# freesoc_1_1.net
KiCad netlist of a schematic drawn in EAGLE
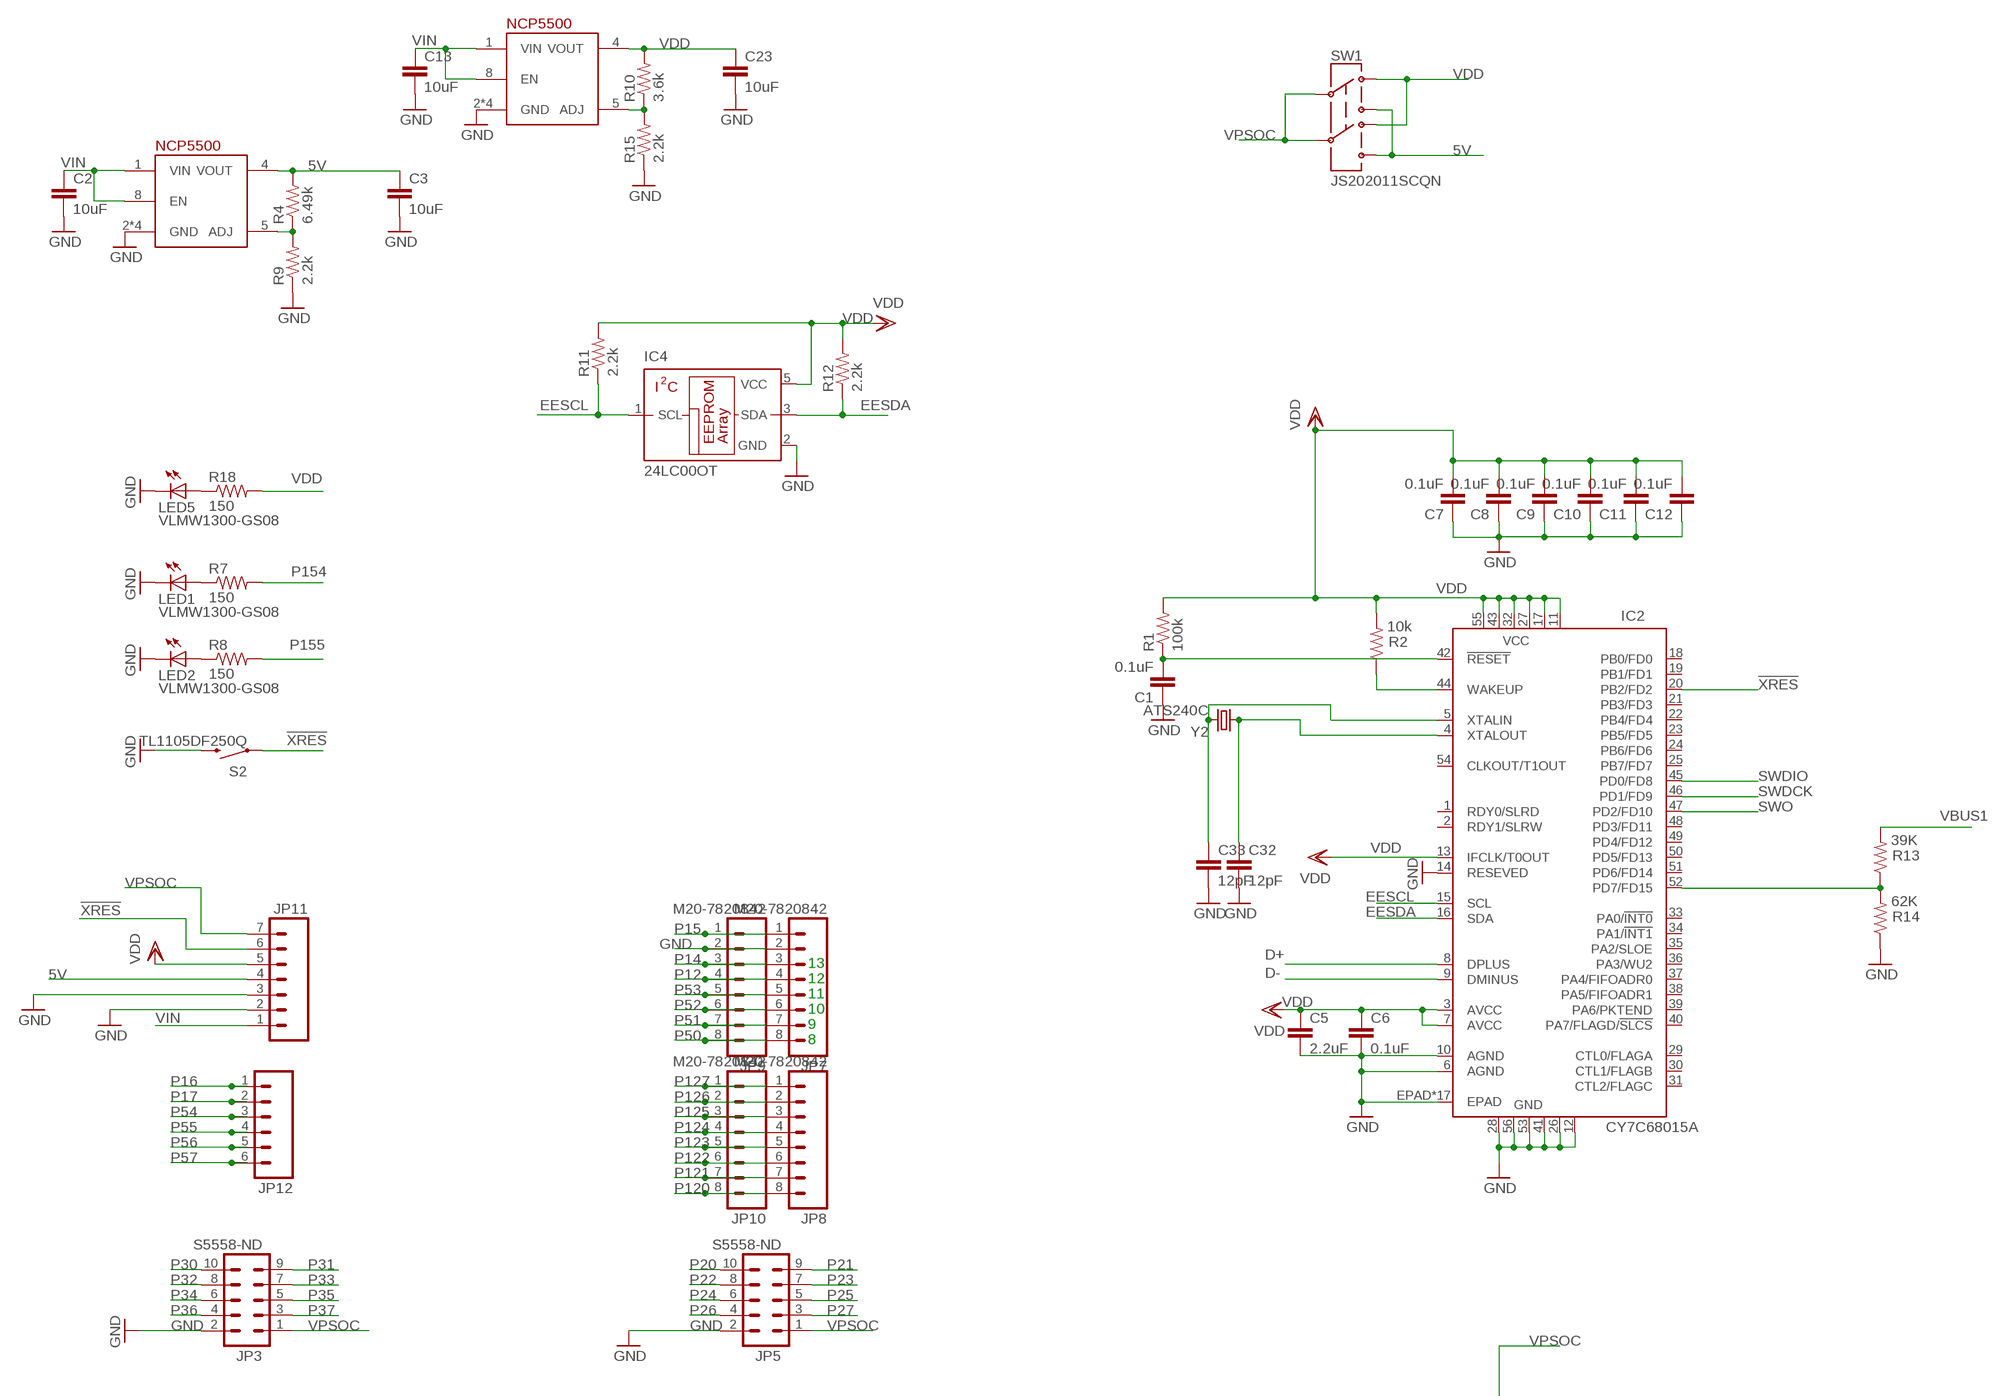
[diagram p0: schematic, sheet 1, part 1 of 2]
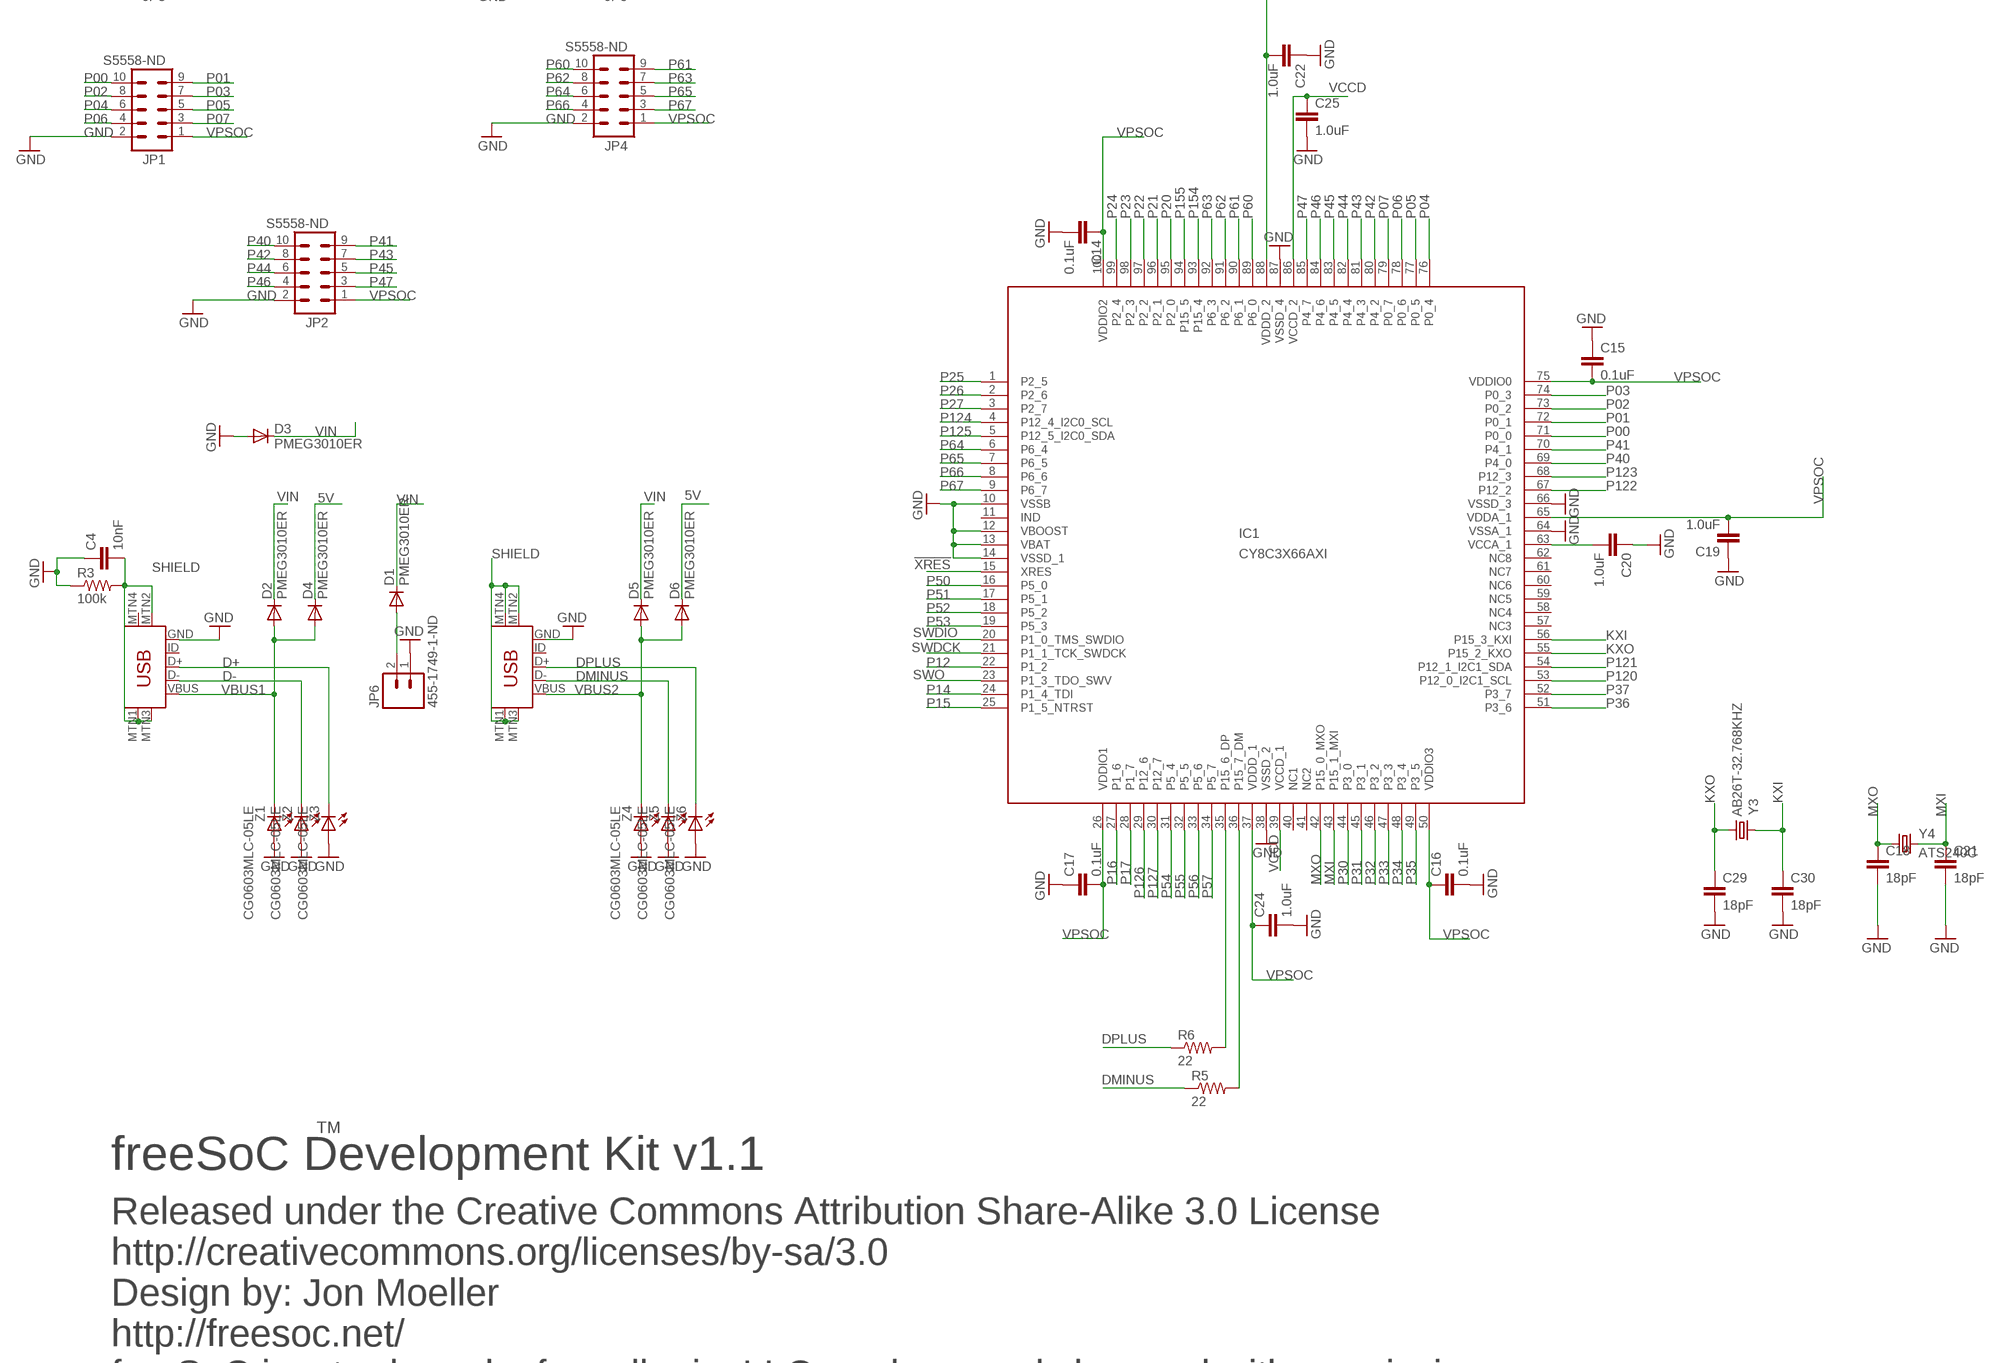
[diagram p1: schematic, sheet 1, part 2 of 2]

(export (version "E")
  (design (tool "Eeschema 10.0.6"))
  (components
    (comp (ref "C1")
      (value "0.1uF")
      (footprint "eagle-import:0402-CAP")
      (libsource (lib "eagle-import") (part "CAP0402-CAP"))
    )
    (comp (ref "C2")
      (value "10uF")
      (footprint "eagle-import:0805")
      (libsource (lib "eagle-import") (part "CAP0805"))
    )
    (comp (ref "C3")
      (value "10uF")
      (footprint "eagle-import:0805")
      (libsource (lib "eagle-import") (part "CAP0805"))
    )
    (comp (ref "C4")
      (value "10nF")
      (footprint "eagle-import:0402-CAP")
      (libsource (lib "eagle-import") (part "CAP0402-CAP"))
    )
    (comp (ref "C5")
      (value "2.2uF")
      (footprint "eagle-import:0603-CAP")
      (libsource (lib "eagle-import") (part "CAP0603-CAP"))
    )
    (comp (ref "C6")
      (value "0.1uF")
      (footprint "eagle-import:0402-CAP")
      (libsource (lib "eagle-import") (part "CAP0402-CAP"))
    )
    (comp (ref "C7")
      (value "0.1uF")
      (footprint "eagle-import:0402-CAP")
      (libsource (lib "eagle-import") (part "CAP0402-CAP"))
    )
    (comp (ref "C8")
      (value "0.1uF")
      (footprint "eagle-import:0402-CAP")
      (libsource (lib "eagle-import") (part "CAP0402-CAP"))
    )
    (comp (ref "C9")
      (value "0.1uF")
      (footprint "eagle-import:0402-CAP")
      (libsource (lib "eagle-import") (part "CAP0402-CAP"))
    )
    (comp (ref "C10")
      (value "0.1uF")
      (footprint "eagle-import:0402-CAP")
      (libsource (lib "eagle-import") (part "CAP0402-CAP"))
    )
    (comp (ref "C11")
      (value "0.1uF")
      (footprint "eagle-import:0402-CAP")
      (libsource (lib "eagle-import") (part "CAP0402-CAP"))
    )
    (comp (ref "C12")
      (value "0.1uF")
      (footprint "eagle-import:0402-CAP")
      (libsource (lib "eagle-import") (part "CAP0402-CAP"))
    )
    (comp (ref "C13")
      (value "10uF")
      (footprint "eagle-import:0805")
      (libsource (lib "eagle-import") (part "CAP0805"))
    )
    (comp (ref "C14")
      (value "0.1uF")
      (footprint "eagle-import:0402-CAP")
      (libsource (lib "eagle-import") (part "CAP0402-CAP"))
    )
    (comp (ref "C15")
      (value "0.1uF")
      (footprint "eagle-import:0402-CAP")
      (libsource (lib "eagle-import") (part "CAP0402-CAP"))
    )
    (comp (ref "C16")
      (value "0.1uF")
      (footprint "eagle-import:0402-CAP")
      (libsource (lib "eagle-import") (part "CAP0402-CAP"))
    )
    (comp (ref "C17")
      (value "0.1uF")
      (footprint "eagle-import:0402-CAP")
      (libsource (lib "eagle-import") (part "CAP0402-CAP"))
    )
    (comp (ref "C18")
      (value "18pF")
      (footprint "eagle-import:0402-CAP")
      (libsource (lib "eagle-import") (part "CAP0402-CAP"))
    )
    (comp (ref "C19")
      (value "1.0uF")
      (footprint "eagle-import:0402-CAP")
      (libsource (lib "eagle-import") (part "CAP0402-CAP"))
    )
    (comp (ref "C20")
      (value "1.0uF")
      (footprint "eagle-import:0402-CAP")
      (libsource (lib "eagle-import") (part "CAP0402-CAP"))
    )
    (comp (ref "C21")
      (value "18pF")
      (footprint "eagle-import:0402-CAP")
      (libsource (lib "eagle-import") (part "CAP0402-CAP"))
    )
    (comp (ref "C22")
      (value "1.0uF")
      (footprint "eagle-import:0402-CAP")
      (libsource (lib "eagle-import") (part "CAP0402-CAP"))
    )
    (comp (ref "C23")
      (value "10uF")
      (footprint "eagle-import:0805")
      (libsource (lib "eagle-import") (part "CAP0805"))
    )
    (comp (ref "C24")
      (value "1.0uF")
      (footprint "eagle-import:0402-CAP")
      (libsource (lib "eagle-import") (part "CAP0402-CAP"))
    )
    (comp (ref "C25")
      (value "1.0uF")
      (footprint "eagle-import:0402-CAP")
      (libsource (lib "eagle-import") (part "CAP0402-CAP"))
    )
    (comp (ref "C29")
      (value "18pF")
      (footprint "eagle-import:0402-CAP")
      (libsource (lib "eagle-import") (part "CAP0402-CAP"))
    )
    (comp (ref "C30")
      (value "18pF")
      (footprint "eagle-import:0402-CAP")
      (libsource (lib "eagle-import") (part "CAP0402-CAP"))
    )
    (comp (ref "C32")
      (value "12pF")
      (footprint "eagle-import:0402-CAP")
      (libsource (lib "eagle-import") (part "CAP0402-CAP"))
    )
    (comp (ref "C33")
      (value "12pF")
      (footprint "eagle-import:0402-CAP")
      (libsource (lib "eagle-import") (part "CAP0402-CAP"))
    )
    (comp (ref "D1")
      (value "PMEG3010ER")
      (footprint "eagle-import:SOD123")
      (libsource (lib "eagle-import") (part "DIODE-SOD123"))
    )
    (comp (ref "D2")
      (value "PMEG3010ER")
      (footprint "eagle-import:SOD123")
      (libsource (lib "eagle-import") (part "DIODE-SOD123"))
    )
    (comp (ref "D3")
      (value "PMEG3010ER")
      (footprint "eagle-import:SOD123")
      (libsource (lib "eagle-import") (part "DIODE-SOD123"))
    )
    (comp (ref "D4")
      (value "PMEG3010ER")
      (footprint "eagle-import:SOD123")
      (libsource (lib "eagle-import") (part "DIODE-SOD123"))
    )
    (comp (ref "D5")
      (value "PMEG3010ER")
      (footprint "eagle-import:SOD123")
      (libsource (lib "eagle-import") (part "DIODE-SOD123"))
    )
    (comp (ref "D6")
      (value "PMEG3010ER")
      (footprint "eagle-import:SOD123")
      (libsource (lib "eagle-import") (part "DIODE-SOD123"))
    )
    (comp (ref "IC1")
      (value "CY8C3X66AXI")
      (footprint "eagle-import:TQFP-100")
      (libsource (lib "eagle-import") (part "CY8C3X66AXI"))
    )
    (comp (ref "IC2")
      (value "CY7C68015A")
      (footprint "eagle-import:QFN56")
      (libsource (lib "eagle-import") (part "CY7C6801A-56QFNLFXC5"))
    )
    (comp (ref "IC4")
      (value "24LC00OT")
      (footprint "eagle-import:SOT23-5L")
      (libsource (lib "eagle-import") (part "2400OTLC"))
    )
    (comp (ref "JP1")
      (value "S5558-ND")
      (footprint "eagle-import:2X5-NS")
      (libsource (lib "eagle-import") (part "M05X2BLANK"))
    )
    (comp (ref "JP2")
      (value "S5558-ND")
      (footprint "eagle-import:2X5-NS")
      (libsource (lib "eagle-import") (part "M05X2BLANK"))
    )
    (comp (ref "JP3")
      (value "S5558-ND")
      (footprint "eagle-import:2X5-NS")
      (libsource (lib "eagle-import") (part "M05X2BLANK"))
    )
    (comp (ref "JP4")
      (value "S5558-ND")
      (footprint "eagle-import:2X5-NS")
      (libsource (lib "eagle-import") (part "M05X2BLANK"))
    )
    (comp (ref "JP5")
      (value "S5558-ND")
      (footprint "eagle-import:2X5-NS")
      (libsource (lib "eagle-import") (part "M05X2BLANK"))
    )
    (comp (ref "JP6")
      (value "455-1749-1-ND")
      (footprint "eagle-import:JST-2-SMD")
      (libsource (lib "eagle-import") (part "M02-JST-2MM-SMT"))
    )
    (comp (ref "JP7")
      (value "M20-7820842")
      (footprint "eagle-import:1X08")
      (libsource (lib "eagle-import") (part "M081X08"))
    )
    (comp (ref "JP8")
      (value "M20-7820842")
      (footprint "eagle-import:1X08")
      (libsource (lib "eagle-import") (part "M081X08"))
    )
    (comp (ref "JP9")
      (value "M20-7820842")
      (footprint "eagle-import:1X08")
      (libsource (lib "eagle-import") (part "M081X08"))
    )
    (comp (ref "JP10")
      (value "M20-7820842")
      (footprint "eagle-import:1X08")
      (libsource (lib "eagle-import") (part "M081X08"))
    )
    (comp (ref "JP11")
      (value "M07")
      (footprint "eagle-import:1X07")
      (libsource (lib "eagle-import") (part "M07"))
    )
    (comp (ref "JP12")
      (value "M06SIP")
      (footprint "eagle-import:1X06")
      (libsource (lib "eagle-import") (part "M06SIP"))
    )
    (comp (ref "LED1")
      (value "VLMW1300-GS08")
      (footprint "eagle-import:LED-0603")
      (libsource (lib "eagle-import") (part "LED0603"))
    )
    (comp (ref "LED2")
      (value "VLMW1300-GS08")
      (footprint "eagle-import:LED-0603")
      (libsource (lib "eagle-import") (part "LED0603"))
    )
    (comp (ref "LED5")
      (value "VLMW1300-GS08")
      (footprint "eagle-import:LED-0603")
      (libsource (lib "eagle-import") (part "LED0603"))
    )
    (comp (ref "R1")
      (value "100k")
      (footprint "eagle-import:0402-RES")
      (libsource (lib "eagle-import") (part "RESISTOR0402-RES"))
    )
    (comp (ref "R2")
      (value "10k")
      (footprint "eagle-import:0402-RES")
      (libsource (lib "eagle-import") (part "RESISTOR0402-RES"))
    )
    (comp (ref "R3")
      (value "100k")
      (footprint "eagle-import:0402-RES")
      (libsource (lib "eagle-import") (part "RESISTOR0402-RES"))
    )
    (comp (ref "R4")
      (value "6.49k")
      (footprint "eagle-import:0402-RES")
      (libsource (lib "eagle-import") (part "RESISTOR0402-RES"))
    )
    (comp (ref "R5")
      (value "22")
      (footprint "eagle-import:0805")
      (libsource (lib "eagle-import") (part "RESISTOR0805-RES"))
    )
    (comp (ref "R6")
      (value "22")
      (footprint "eagle-import:0805")
      (libsource (lib "eagle-import") (part "RESISTOR0805-RES"))
    )
    (comp (ref "R7")
      (value "150")
      (footprint "eagle-import:0603-RES")
      (libsource (lib "eagle-import") (part "RESISTOR0603-RES"))
    )
    (comp (ref "R8")
      (value "150")
      (footprint "eagle-import:0603-RES")
      (libsource (lib "eagle-import") (part "RESISTOR0603-RES"))
    )
    (comp (ref "R9")
      (value "2.2k")
      (footprint "eagle-import:0402-RES")
      (libsource (lib "eagle-import") (part "RESISTOR0402-RES"))
    )
    (comp (ref "R10")
      (value "3.6k")
      (footprint "eagle-import:0402-RES")
      (libsource (lib "eagle-import") (part "RESISTOR0402-RES"))
    )
    (comp (ref "R11")
      (value "2.2k")
      (footprint "eagle-import:0402-RES")
      (libsource (lib "eagle-import") (part "RESISTOR0402-RES"))
    )
    (comp (ref "R12")
      (value "2.2k")
      (footprint "eagle-import:0402-RES")
      (libsource (lib "eagle-import") (part "RESISTOR0402-RES"))
    )
    (comp (ref "R13")
      (value "39K")
      (footprint "eagle-import:0402-RES")
      (libsource (lib "eagle-import") (part "RESISTOR0402-RES"))
    )
    (comp (ref "R14")
      (value "62K")
      (footprint "eagle-import:0402-RES")
      (libsource (lib "eagle-import") (part "RESISTOR0402-RES"))
    )
    (comp (ref "R15")
      (value "2.2k")
      (footprint "eagle-import:0402-RES")
      (libsource (lib "eagle-import") (part "RESISTOR0402-RES"))
    )
    (comp (ref "R18")
      (value "150")
      (footprint "eagle-import:0603-RES")
      (libsource (lib "eagle-import") (part "RESISTOR0603-RES"))
    )
    (comp (ref "REG3V3")
      (value "NCP5500")
      (footprint "eagle-import:SO08")
      (libsource (lib "eagle-import") (part "NCP5500"))
    )
    (comp (ref "REG5V0")
      (value "NCP5500")
      (footprint "eagle-import:SO08")
      (libsource (lib "eagle-import") (part "NCP5500"))
    )
    (comp (ref "S2")
      (value "TL1105DF250Q")
      (footprint "eagle-import:TACTILE-PTH")
      (libsource (lib "eagle-import") (part "SWITCH-MOMENTARY-2PTH"))
    )
    (comp (ref "SW1")
      (value "JS202011SCQN")
      (footprint "eagle-import:JS202011SCQN")
      (libsource (lib "eagle-import") (part "JS202011SCQN"))
    )
    (comp (ref "U$5")
      (value "USB-MINIB-5PIN")
      (footprint "eagle-import:USB-MINIB")
      (libsource (lib "eagle-import") (part "USB-MINIB-5PIN"))
    )
    (comp (ref "U$6")
      (value "USB-MINIB-5PIN")
      (footprint "eagle-import:USB-MINIB")
      (libsource (lib "eagle-import") (part "USB-MINIB-5PIN"))
    )
    (comp (ref "Y2")
      (value "ATS240C")
      (footprint "eagle-import:HC49US")
      (libsource (lib "eagle-import") (part "CRYSTALHC49US"))
    )
    (comp (ref "Y3")
      (value "AB26T-32.768KHZ")
      (footprint "eagle-import:CRYSTAL-32KHZ-SMD")
      (libsource (lib "eagle-import") (part "CRYSTAL32-SMD"))
    )
    (comp (ref "Y4")
      (value "ATS240C")
      (footprint "eagle-import:HC49US")
      (libsource (lib "eagle-import") (part "CRYSTALHC49US"))
    )
    (comp (ref "Z1")
      (value "CG0603MLC-05LE")
      (footprint "eagle-import:LED-0603")
      (libsource (lib "eagle-import") (part "LED0603"))
    )
    (comp (ref "Z2")
      (value "CG0603MLC-05LE")
      (footprint "eagle-import:LED-0603")
      (libsource (lib "eagle-import") (part "LED0603"))
    )
    (comp (ref "Z3")
      (value "CG0603MLC-05LE")
      (footprint "eagle-import:LED-0603")
      (libsource (lib "eagle-import") (part "LED0603"))
    )
    (comp (ref "Z4")
      (value "CG0603MLC-05LE")
      (footprint "eagle-import:LED-0603")
      (libsource (lib "eagle-import") (part "LED0603"))
    )
    (comp (ref "Z5")
      (value "CG0603MLC-05LE")
      (footprint "eagle-import:LED-0603")
      (libsource (lib "eagle-import") (part "LED0603"))
    )
    (comp (ref "Z6")
      (value "CG0603MLC-05LE")
      (footprint "eagle-import:LED-0603")
      (libsource (lib "eagle-import") (part "LED0603"))
    )
  )
  (nets
    (net (code "1") (name "/5V") (class "Default")
      (node (ref "C3") (pin "1") (pinfunction "1_1") (pintype "passive"))
      (node (ref "D4") (pin "C") (pinfunction "C_C") (pintype "passive"))
      (node (ref "D6") (pin "C") (pinfunction "C_C") (pintype "passive"))
      (node (ref "JP11") (pin "4") (pinfunction "4_4") (pintype "passive"))
      (node (ref "R4") (pin "2") (pinfunction "2_2") (pintype "passive"))
      (node (ref "REG5V0") (pin "4") (pinfunction "VOUT_4") (pintype "bidirectional"))
      (node (ref "SW1") (pin "B1") (pinfunction "B1_B1") (pintype "bidirectional"))
      (node (ref "SW1") (pin "B2") (pinfunction "B2_B2") (pintype "bidirectional"))
    )
    (net (code "2") (name "/D+") (class "Default")
      (node (ref "IC2") (pin "8") (pinfunction "DPLUS_8") (pintype "bidirectional"))
      (node (ref "U$5") (pin "D+") (pinfunction "D+_D+") (pintype "bidirectional"))
      (node (ref "Z3") (pin "C") (pinfunction "C_C") (pintype "passive"))
    )
    (net (code "3") (name "/D-") (class "Default")
      (node (ref "IC2") (pin "9") (pinfunction "DMINUS_9") (pintype "bidirectional"))
      (node (ref "U$5") (pin "D-") (pinfunction "D-_D-") (pintype "bidirectional"))
      (node (ref "Z2") (pin "C") (pinfunction "C_C") (pintype "passive"))
    )
    (net (code "4") (name "/DMINUS") (class "Default")
      (node (ref "R5") (pin "1") (pinfunction "1_1") (pintype "passive"))
      (node (ref "U$6") (pin "D-") (pinfunction "D-_D-") (pintype "bidirectional"))
      (node (ref "Z5") (pin "C") (pinfunction "C_C") (pintype "passive"))
    )
    (net (code "5") (name "/DPLUS") (class "Default")
      (node (ref "R6") (pin "1") (pinfunction "1_1") (pintype "passive"))
      (node (ref "U$6") (pin "D+") (pinfunction "D+_D+") (pintype "bidirectional"))
      (node (ref "Z6") (pin "C") (pinfunction "C_C") (pintype "passive"))
    )
    (net (code "6") (name "/EESCL") (class "Default")
      (node (ref "IC2") (pin "15") (pinfunction "SCL_15") (pintype "output"))
      (node (ref "IC4") (pin "1") (pinfunction "SCL_1") (pintype "input"))
      (node (ref "R11") (pin "1") (pinfunction "1_1") (pintype "passive"))
    )
    (net (code "7") (name "/EESDA") (class "Default")
      (node (ref "IC2") (pin "16") (pinfunction "SDA_16") (pintype "bidirectional"))
      (node (ref "IC4") (pin "3") (pinfunction "SDA_3") (pintype "bidirectional"))
      (node (ref "R12") (pin "1") (pinfunction "1_1") (pintype "passive"))
    )
    (net (code "8") (name "/KXI") (class "Default")
      (node (ref "C30") (pin "1") (pinfunction "1_1") (pintype "passive"))
      (node (ref "IC1") (pin "56") (pinfunction "P15_3_KXI_56") (pintype "passive"))
      (node (ref "Y3") (pin "X1") (pinfunction "1_X1") (pintype "passive"))
    )
    (net (code "9") (name "/KXO") (class "Default")
      (node (ref "C29") (pin "1") (pinfunction "1_1") (pintype "passive"))
      (node (ref "IC1") (pin "55") (pinfunction "P15_2_KXO_55") (pintype "passive"))
      (node (ref "Y3") (pin "X2") (pinfunction "2_X2") (pintype "passive"))
    )
    (net (code "10") (name "/MXI") (class "Default")
      (node (ref "C21") (pin "1") (pinfunction "1_1") (pintype "passive"))
      (node (ref "IC1") (pin "43") (pinfunction "P15_1_MXI_43") (pintype "passive"))
      (node (ref "Y4") (pin "2") (pinfunction "2_2") (pintype "passive"))
    )
    (net (code "11") (name "/MXO") (class "Default")
      (node (ref "C18") (pin "1") (pinfunction "1_1") (pintype "passive"))
      (node (ref "IC1") (pin "42") (pinfunction "P15_0_MXO_42") (pintype "passive"))
      (node (ref "Y4") (pin "1") (pinfunction "1_1") (pintype "passive"))
    )
    (net (code "12") (name "/P00") (class "Default")
      (node (ref "IC1") (pin "71") (pinfunction "P0_0_71") (pintype "passive"))
      (node (ref "JP1") (pin "10") (pinfunction "10_10") (pintype "passive"))
    )
    (net (code "13") (name "/P01") (class "Default")
      (node (ref "IC1") (pin "72") (pinfunction "P0_1_72") (pintype "passive"))
      (node (ref "JP1") (pin "9") (pinfunction "9_9") (pintype "passive"))
    )
    (net (code "14") (name "/P02") (class "Default")
      (node (ref "IC1") (pin "73") (pinfunction "P0_2_73") (pintype "passive"))
      (node (ref "JP1") (pin "8") (pinfunction "8_8") (pintype "passive"))
    )
    (net (code "15") (name "/P03") (class "Default")
      (node (ref "IC1") (pin "74") (pinfunction "P0_3_74") (pintype "passive"))
      (node (ref "JP1") (pin "7") (pinfunction "7_7") (pintype "passive"))
    )
    (net (code "16") (name "/P04") (class "Default")
      (node (ref "IC1") (pin "76") (pinfunction "P0_4_76") (pintype "passive"))
      (node (ref "JP1") (pin "6") (pinfunction "6_6") (pintype "passive"))
    )
    (net (code "17") (name "/P05") (class "Default")
      (node (ref "IC1") (pin "77") (pinfunction "P0_5_77") (pintype "passive"))
      (node (ref "JP1") (pin "5") (pinfunction "5_5") (pintype "passive"))
    )
    (net (code "18") (name "/P06") (class "Default")
      (node (ref "IC1") (pin "78") (pinfunction "P0_6_78") (pintype "passive"))
      (node (ref "JP1") (pin "4") (pinfunction "4_4") (pintype "passive"))
    )
    (net (code "19") (name "/P07") (class "Default")
      (node (ref "IC1") (pin "79") (pinfunction "P0_7_79") (pintype "passive"))
      (node (ref "JP1") (pin "3") (pinfunction "3_3") (pintype "passive"))
    )
    (net (code "20") (name "/P12") (class "Default")
      (node (ref "IC1") (pin "22") (pinfunction "P1_2_22") (pintype "passive"))
      (node (ref "JP7") (pin "4") (pinfunction "4_4") (pintype "passive"))
      (node (ref "JP9") (pin "4") (pinfunction "4_4") (pintype "passive"))
    )
    (net (code "21") (name "/P14") (class "Default")
      (node (ref "IC1") (pin "24") (pinfunction "P1_4_TDI_24") (pintype "passive"))
      (node (ref "JP7") (pin "3") (pinfunction "3_3") (pintype "passive"))
      (node (ref "JP9") (pin "3") (pinfunction "3_3") (pintype "passive"))
    )
    (net (code "22") (name "/P15") (class "Default")
      (node (ref "IC1") (pin "25") (pinfunction "P1_5_NTRST_25") (pintype "passive"))
      (node (ref "JP7") (pin "1") (pinfunction "1_1") (pintype "passive"))
      (node (ref "JP9") (pin "1") (pinfunction "1_1") (pintype "passive"))
    )
    (net (code "23") (name "/P16") (class "Default")
      (node (ref "IC1") (pin "27") (pinfunction "P1_6_27") (pintype "passive"))
      (node (ref "JP12") (pin "1") (pinfunction "1_1") (pintype "passive"))
    )
    (net (code "24") (name "/P17") (class "Default")
      (node (ref "IC1") (pin "28") (pinfunction "P1_7_28") (pintype "passive"))
      (node (ref "JP12") (pin "2") (pinfunction "2_2") (pintype "passive"))
    )
    (net (code "25") (name "/P20") (class "Default")
      (node (ref "IC1") (pin "95") (pinfunction "P2_0_95") (pintype "passive"))
      (node (ref "JP5") (pin "10") (pinfunction "10_10") (pintype "passive"))
    )
    (net (code "26") (name "/P21") (class "Default")
      (node (ref "IC1") (pin "96") (pinfunction "P2_1_96") (pintype "passive"))
      (node (ref "JP5") (pin "9") (pinfunction "9_9") (pintype "passive"))
    )
    (net (code "27") (name "/P22") (class "Default")
      (node (ref "IC1") (pin "97") (pinfunction "P2_2_97") (pintype "passive"))
      (node (ref "JP5") (pin "8") (pinfunction "8_8") (pintype "passive"))
    )
    (net (code "28") (name "/P23") (class "Default")
      (node (ref "IC1") (pin "98") (pinfunction "P2_3_98") (pintype "passive"))
      (node (ref "JP5") (pin "7") (pinfunction "7_7") (pintype "passive"))
    )
    (net (code "29") (name "/P24") (class "Default")
      (node (ref "IC1") (pin "99") (pinfunction "P2_4_99") (pintype "passive"))
      (node (ref "JP5") (pin "6") (pinfunction "6_6") (pintype "passive"))
    )
    (net (code "30") (name "/P25") (class "Default")
      (node (ref "IC1") (pin "1") (pinfunction "P2_5_1") (pintype "passive"))
      (node (ref "JP5") (pin "5") (pinfunction "5_5") (pintype "passive"))
    )
    (net (code "31") (name "/P26") (class "Default")
      (node (ref "IC1") (pin "2") (pinfunction "P2_6_2") (pintype "passive"))
      (node (ref "JP5") (pin "4") (pinfunction "4_4") (pintype "passive"))
    )
    (net (code "32") (name "/P27") (class "Default")
      (node (ref "IC1") (pin "3") (pinfunction "P2_7_3") (pintype "passive"))
      (node (ref "JP5") (pin "3") (pinfunction "3_3") (pintype "passive"))
    )
    (net (code "33") (name "/P30") (class "Default")
      (node (ref "IC1") (pin "44") (pinfunction "P3_0_44") (pintype "passive"))
      (node (ref "JP3") (pin "10") (pinfunction "10_10") (pintype "passive"))
    )
    (net (code "34") (name "/P31") (class "Default")
      (node (ref "IC1") (pin "45") (pinfunction "P3_1_45") (pintype "passive"))
      (node (ref "JP3") (pin "9") (pinfunction "9_9") (pintype "passive"))
    )
    (net (code "35") (name "/P32") (class "Default")
      (node (ref "IC1") (pin "46") (pinfunction "P3_2_46") (pintype "passive"))
      (node (ref "JP3") (pin "8") (pinfunction "8_8") (pintype "passive"))
    )
    (net (code "36") (name "/P33") (class "Default")
      (node (ref "IC1") (pin "47") (pinfunction "P3_3_47") (pintype "passive"))
      (node (ref "JP3") (pin "7") (pinfunction "7_7") (pintype "passive"))
    )
    (net (code "37") (name "/P34") (class "Default")
      (node (ref "IC1") (pin "48") (pinfunction "P3_4_48") (pintype "passive"))
      (node (ref "JP3") (pin "6") (pinfunction "6_6") (pintype "passive"))
    )
    (net (code "38") (name "/P35") (class "Default")
      (node (ref "IC1") (pin "49") (pinfunction "P3_5_49") (pintype "passive"))
      (node (ref "JP3") (pin "5") (pinfunction "5_5") (pintype "passive"))
    )
    (net (code "39") (name "/P36") (class "Default")
      (node (ref "IC1") (pin "51") (pinfunction "P3_6_51") (pintype "passive"))
      (node (ref "JP3") (pin "4") (pinfunction "4_4") (pintype "passive"))
    )
    (net (code "40") (name "/P37") (class "Default")
      (node (ref "IC1") (pin "52") (pinfunction "P3_7_52") (pintype "passive"))
      (node (ref "JP3") (pin "3") (pinfunction "3_3") (pintype "passive"))
    )
    (net (code "41") (name "/P40") (class "Default")
      (node (ref "IC1") (pin "69") (pinfunction "P4_0_69") (pintype "passive"))
      (node (ref "JP2") (pin "10") (pinfunction "10_10") (pintype "passive"))
    )
    (net (code "42") (name "/P41") (class "Default")
      (node (ref "IC1") (pin "70") (pinfunction "P4_1_70") (pintype "passive"))
      (node (ref "JP2") (pin "9") (pinfunction "9_9") (pintype "passive"))
    )
    (net (code "43") (name "/P42") (class "Default")
      (node (ref "IC1") (pin "80") (pinfunction "P4_2_80") (pintype "passive"))
      (node (ref "JP2") (pin "8") (pinfunction "8_8") (pintype "passive"))
    )
    (net (code "44") (name "/P43") (class "Default")
      (node (ref "IC1") (pin "81") (pinfunction "P4_3_81") (pintype "passive"))
      (node (ref "JP2") (pin "7") (pinfunction "7_7") (pintype "passive"))
    )
    (net (code "45") (name "/P44") (class "Default")
      (node (ref "IC1") (pin "82") (pinfunction "P4_4_82") (pintype "passive"))
      (node (ref "JP2") (pin "6") (pinfunction "6_6") (pintype "passive"))
    )
    (net (code "46") (name "/P45") (class "Default")
      (node (ref "IC1") (pin "83") (pinfunction "P4_5_83") (pintype "passive"))
      (node (ref "JP2") (pin "5") (pinfunction "5_5") (pintype "passive"))
    )
    (net (code "47") (name "/P46") (class "Default")
      (node (ref "IC1") (pin "84") (pinfunction "P4_6_84") (pintype "passive"))
      (node (ref "JP2") (pin "4") (pinfunction "4_4") (pintype "passive"))
    )
    (net (code "48") (name "/P47") (class "Default")
      (node (ref "IC1") (pin "85") (pinfunction "P4_7_85") (pintype "passive"))
      (node (ref "JP2") (pin "3") (pinfunction "3_3") (pintype "passive"))
    )
    (net (code "49") (name "/P50") (class "Default")
      (node (ref "IC1") (pin "16") (pinfunction "P5_0_16") (pintype "passive"))
      (node (ref "JP7") (pin "8") (pinfunction "8_8") (pintype "passive"))
      (node (ref "JP9") (pin "8") (pinfunction "8_8") (pintype "passive"))
    )
    (net (code "50") (name "/P51") (class "Default")
      (node (ref "IC1") (pin "17") (pinfunction "P5_1_17") (pintype "passive"))
      (node (ref "JP7") (pin "7") (pinfunction "7_7") (pintype "passive"))
      (node (ref "JP9") (pin "7") (pinfunction "7_7") (pintype "passive"))
    )
    (net (code "51") (name "/P52") (class "Default")
      (node (ref "IC1") (pin "18") (pinfunction "P5_2_18") (pintype "passive"))
      (node (ref "JP7") (pin "6") (pinfunction "6_6") (pintype "passive"))
      (node (ref "JP9") (pin "6") (pinfunction "6_6") (pintype "passive"))
    )
    (net (code "52") (name "/P53") (class "Default")
      (node (ref "IC1") (pin "19") (pinfunction "P5_3_19") (pintype "passive"))
      (node (ref "JP7") (pin "5") (pinfunction "5_5") (pintype "passive"))
      (node (ref "JP9") (pin "5") (pinfunction "5_5") (pintype "passive"))
    )
    (net (code "53") (name "/P54") (class "Default")
      (node (ref "IC1") (pin "31") (pinfunction "P5_4_31") (pintype "passive"))
      (node (ref "JP12") (pin "3") (pinfunction "3_3") (pintype "passive"))
    )
    (net (code "54") (name "/P55") (class "Default")
      (node (ref "IC1") (pin "32") (pinfunction "P5_5_32") (pintype "passive"))
      (node (ref "JP12") (pin "4") (pinfunction "4_4") (pintype "passive"))
    )
    (net (code "55") (name "/P56") (class "Default")
      (node (ref "IC1") (pin "33") (pinfunction "P5_6_33") (pintype "passive"))
      (node (ref "JP12") (pin "5") (pinfunction "5_5") (pintype "passive"))
    )
    (net (code "56") (name "/P57") (class "Default")
      (node (ref "IC1") (pin "34") (pinfunction "P5_7_34") (pintype "passive"))
      (node (ref "JP12") (pin "6") (pinfunction "6_6") (pintype "passive"))
    )
    (net (code "57") (name "/P60") (class "Default")
      (node (ref "IC1") (pin "89") (pinfunction "P6_0_89") (pintype "passive"))
      (node (ref "JP4") (pin "10") (pinfunction "10_10") (pintype "passive"))
    )
    (net (code "58") (name "/P61") (class "Default")
      (node (ref "IC1") (pin "90") (pinfunction "P6_1_90") (pintype "passive"))
      (node (ref "JP4") (pin "9") (pinfunction "9_9") (pintype "passive"))
    )
    (net (code "59") (name "/P62") (class "Default")
      (node (ref "IC1") (pin "91") (pinfunction "P6_2_91") (pintype "passive"))
      (node (ref "JP4") (pin "8") (pinfunction "8_8") (pintype "passive"))
    )
    (net (code "60") (name "/P63") (class "Default")
      (node (ref "IC1") (pin "92") (pinfunction "P6_3_92") (pintype "passive"))
      (node (ref "JP4") (pin "7") (pinfunction "7_7") (pintype "passive"))
    )
    (net (code "61") (name "/P64") (class "Default")
      (node (ref "IC1") (pin "6") (pinfunction "P6_4_6") (pintype "passive"))
      (node (ref "JP4") (pin "6") (pinfunction "6_6") (pintype "passive"))
    )
    (net (code "62") (name "/P65") (class "Default")
      (node (ref "IC1") (pin "7") (pinfunction "P6_5_7") (pintype "passive"))
      (node (ref "JP4") (pin "5") (pinfunction "5_5") (pintype "passive"))
    )
    (net (code "63") (name "/P66") (class "Default")
      (node (ref "IC1") (pin "8") (pinfunction "P6_6_8") (pintype "passive"))
      (node (ref "JP4") (pin "4") (pinfunction "4_4") (pintype "passive"))
    )
    (net (code "64") (name "/P67") (class "Default")
      (node (ref "IC1") (pin "9") (pinfunction "P6_7_9") (pintype "passive"))
      (node (ref "JP4") (pin "3") (pinfunction "3_3") (pintype "passive"))
    )
    (net (code "65") (name "/P120") (class "Default")
      (node (ref "IC1") (pin "53") (pinfunction "P12_0_I2C1_SCL_53") (pintype "passive"))
      (node (ref "JP10") (pin "8") (pinfunction "8_8") (pintype "passive"))
      (node (ref "JP8") (pin "8") (pinfunction "8_8") (pintype "passive"))
    )
    (net (code "66") (name "/P121") (class "Default")
      (node (ref "IC1") (pin "54") (pinfunction "P12_1_I2C1_SDA_54") (pintype "passive"))
      (node (ref "JP10") (pin "7") (pinfunction "7_7") (pintype "passive"))
      (node (ref "JP8") (pin "7") (pinfunction "7_7") (pintype "passive"))
    )
    (net (code "67") (name "/P122") (class "Default")
      (node (ref "IC1") (pin "67") (pinfunction "P12_2_67") (pintype "passive"))
      (node (ref "JP10") (pin "6") (pinfunction "6_6") (pintype "passive"))
      (node (ref "JP8") (pin "6") (pinfunction "6_6") (pintype "passive"))
    )
    (net (code "68") (name "/P123") (class "Default")
      (node (ref "IC1") (pin "68") (pinfunction "P12_3_68") (pintype "passive"))
      (node (ref "JP10") (pin "5") (pinfunction "5_5") (pintype "passive"))
      (node (ref "JP8") (pin "5") (pinfunction "5_5") (pintype "passive"))
    )
    (net (code "69") (name "/P124") (class "Default")
      (node (ref "IC1") (pin "4") (pinfunction "P12_4_I2C0_SCL_4") (pintype "passive"))
      (node (ref "JP10") (pin "4") (pinfunction "4_4") (pintype "passive"))
      (node (ref "JP8") (pin "4") (pinfunction "4_4") (pintype "passive"))
    )
    (net (code "70") (name "/P125") (class "Default")
      (node (ref "IC1") (pin "5") (pinfunction "P12_5_I2C0_SDA_5") (pintype "passive"))
      (node (ref "JP10") (pin "3") (pinfunction "3_3") (pintype "passive"))
      (node (ref "JP8") (pin "3") (pinfunction "3_3") (pintype "passive"))
    )
    (net (code "71") (name "/P126") (class "Default")
      (node (ref "IC1") (pin "29") (pinfunction "P12_6_29") (pintype "passive"))
      (node (ref "JP10") (pin "2") (pinfunction "2_2") (pintype "passive"))
      (node (ref "JP8") (pin "2") (pinfunction "2_2") (pintype "passive"))
    )
    (net (code "72") (name "/P127") (class "Default")
      (node (ref "IC1") (pin "30") (pinfunction "P12_7_30") (pintype "passive"))
      (node (ref "JP10") (pin "1") (pinfunction "1_1") (pintype "passive"))
      (node (ref "JP8") (pin "1") (pinfunction "1_1") (pintype "passive"))
    )
    (net (code "73") (name "/P154") (class "Default")
      (node (ref "IC1") (pin "93") (pinfunction "P15_4_93") (pintype "passive"))
      (node (ref "R7") (pin "2") (pinfunction "2_2") (pintype "passive"))
    )
    (net (code "74") (name "/P155") (class "Default")
      (node (ref "IC1") (pin "94") (pinfunction "P15_5_94") (pintype "passive"))
      (node (ref "R8") (pin "2") (pinfunction "2_2") (pintype "passive"))
    )
    (net (code "75") (name "/SHIELD") (class "Default")
      (node (ref "C4") (pin "2") (pinfunction "2_2") (pintype "passive"))
      (node (ref "R3") (pin "2") (pinfunction "2_2") (pintype "passive"))
      (node (ref "U$5") (pin "MTN1") (pinfunction "MTN2_MTN1") (pintype "bidirectional"))
      (node (ref "U$5") (pin "MTN2") (pinfunction "MTN3_MTN2") (pintype "bidirectional"))
      (node (ref "U$5") (pin "MTN3") (pinfunction "MTN1_MTN3") (pintype "bidirectional"))
      (node (ref "U$6") (pin "MTN1") (pinfunction "MTN2_MTN1") (pintype "bidirectional"))
      (node (ref "U$6") (pin "MTN2") (pinfunction "MTN3_MTN2") (pintype "bidirectional"))
      (node (ref "U$6") (pin "MTN3") (pinfunction "MTN1_MTN3") (pintype "bidirectional"))
      (node (ref "U$6") (pin "MTN4") (pinfunction "MTN4_MTN4") (pintype "bidirectional"))
    )
    (net (code "76") (name "/SWDCK") (class "Default")
      (node (ref "IC1") (pin "21") (pinfunction "P1_1_TCK_SWDCK_21") (pintype "passive"))
      (node (ref "IC2") (pin "46") (pinfunction "PD1/FD9_46") (pintype "bidirectional"))
    )
    (net (code "77") (name "/SWDIO") (class "Default")
      (node (ref "IC1") (pin "20") (pinfunction "P1_0_TMS_SWDIO_20") (pintype "passive"))
      (node (ref "IC2") (pin "45") (pinfunction "PD0/FD8_45") (pintype "bidirectional"))
    )
    (net (code "78") (name "/SWO") (class "Default")
      (node (ref "IC1") (pin "23") (pinfunction "P1_3_TDO_SWV_23") (pintype "passive"))
      (node (ref "IC2") (pin "47") (pinfunction "PD2/FD10_47") (pintype "bidirectional"))
    )
    (net (code "79") (name "/VBUS1") (class "Default")
      (node (ref "D2") (pin "A") (pinfunction "A_A") (pintype "passive"))
      (node (ref "D4") (pin "A") (pinfunction "A_A") (pintype "passive"))
      (node (ref "R13") (pin "2") (pinfunction "2_2") (pintype "passive"))
      (node (ref "U$5") (pin "VBUS") (pinfunction "VBUS_VBUS") (pintype "bidirectional"))
      (node (ref "Z1") (pin "C") (pinfunction "C_C") (pintype "passive"))
    )
    (net (code "80") (name "/VBUS2") (class "Default")
      (node (ref "D5") (pin "A") (pinfunction "A_A") (pintype "passive"))
      (node (ref "D6") (pin "A") (pinfunction "A_A") (pintype "passive"))
      (node (ref "U$6") (pin "VBUS") (pinfunction "VBUS_VBUS") (pintype "bidirectional"))
      (node (ref "Z4") (pin "C") (pinfunction "C_C") (pintype "passive"))
    )
    (net (code "81") (name "/VCCD") (class "Default")
      (node (ref "C25") (pin "1") (pinfunction "1_1") (pintype "passive"))
      (node (ref "IC1") (pin "39") (pinfunction "VCCD_1_39") (pintype "passive"))
      (node (ref "IC1") (pin "86") (pinfunction "VCCD_2_86") (pintype "passive"))
    )
    (net (code "82") (name "/VIN") (class "Default")
      (node (ref "C13") (pin "1") (pinfunction "1_1") (pintype "passive"))
      (node (ref "C2") (pin "1") (pinfunction "1_1") (pintype "passive"))
      (node (ref "D1") (pin "C") (pinfunction "C_C") (pintype "passive"))
      (node (ref "D2") (pin "C") (pinfunction "C_C") (pintype "passive"))
      (node (ref "D3") (pin "C") (pinfunction "C_C") (pintype "passive"))
      (node (ref "D5") (pin "C") (pinfunction "C_C") (pintype "passive"))
      (node (ref "JP11") (pin "1") (pinfunction "1_1") (pintype "passive"))
      (node (ref "REG3V3") (pin "1") (pinfunction "VIN_1") (pintype "bidirectional"))
      (node (ref "REG3V3") (pin "8") (pinfunction "EN_8") (pintype "bidirectional"))
      (node (ref "REG5V0") (pin "1") (pinfunction "VIN_1") (pintype "bidirectional"))
      (node (ref "REG5V0") (pin "8") (pinfunction "EN_8") (pintype "bidirectional"))
    )
    (net (code "83") (name "/VPSOC") (class "Default")
      (node (ref "C14") (pin "1") (pinfunction "1_1") (pintype "passive"))
      (node (ref "C15") (pin "2") (pinfunction "2_2") (pintype "passive"))
      (node (ref "C16") (pin "1") (pinfunction "1_1") (pintype "passive"))
      (node (ref "C17") (pin "2") (pinfunction "2_2") (pintype "passive"))
      (node (ref "C19") (pin "2") (pinfunction "2_2") (pintype "passive"))
      (node (ref "C22") (pin "2") (pinfunction "2_2") (pintype "passive"))
      (node (ref "C24") (pin "1") (pinfunction "1_1") (pintype "passive"))
      (node (ref "IC1") (pin "100") (pinfunction "VDDIO2_100") (pintype "passive"))
      (node (ref "IC1") (pin "26") (pinfunction "VDDIO1_26") (pintype "passive"))
      (node (ref "IC1") (pin "37") (pinfunction "VDDD_1_37") (pintype "passive"))
      (node (ref "IC1") (pin "50") (pinfunction "VDDIO3_50") (pintype "passive"))
      (node (ref "IC1") (pin "65") (pinfunction "VDDA_1_65") (pintype "passive"))
      (node (ref "IC1") (pin "75") (pinfunction "VDDIO0_75") (pintype "passive"))
      (node (ref "IC1") (pin "88") (pinfunction "VDDD_2_88") (pintype "passive"))
      (node (ref "JP1") (pin "1") (pinfunction "1_1") (pintype "passive"))
      (node (ref "JP11") (pin "7") (pinfunction "7_7") (pintype "passive"))
      (node (ref "JP2") (pin "1") (pinfunction "1_1") (pintype "passive"))
      (node (ref "JP3") (pin "1") (pinfunction "1_1") (pintype "passive"))
      (node (ref "JP4") (pin "1") (pinfunction "1_1") (pintype "passive"))
      (node (ref "JP5") (pin "1") (pinfunction "1_1") (pintype "passive"))
      (node (ref "SW1") (pin "C1") (pinfunction "C1_C1") (pintype "bidirectional"))
      (node (ref "SW1") (pin "C2") (pinfunction "C2_C2") (pintype "bidirectional"))
    )
    (net (code "84") (name "/~{XRES}") (class "Default")
      (node (ref "IC1") (pin "15") (pinfunction "XRES_15") (pintype "passive"))
      (node (ref "IC2") (pin "20") (pinfunction "PB2/FD2_20") (pintype "bidirectional"))
      (node (ref "JP11") (pin "6") (pinfunction "6_6") (pintype "passive"))
      (node (ref "S2") (pin "1") (pinfunction "1_1") (pintype "passive"))
    )
    (net (code "85") (name "GND") (class "Default")
      (node (ref "C1") (pin "1") (pinfunction "1_1") (pintype "passive"))
      (node (ref "C10") (pin "1") (pinfunction "1_1") (pintype "passive"))
      (node (ref "C11") (pin "1") (pinfunction "1_1") (pintype "passive"))
      (node (ref "C12") (pin "1") (pinfunction "1_1") (pintype "passive"))
      (node (ref "C13") (pin "2") (pinfunction "2_2") (pintype "passive"))
      (node (ref "C14") (pin "2") (pinfunction "2_2") (pintype "passive"))
      (node (ref "C15") (pin "1") (pinfunction "1_1") (pintype "passive"))
      (node (ref "C16") (pin "2") (pinfunction "2_2") (pintype "passive"))
      (node (ref "C17") (pin "1") (pinfunction "1_1") (pintype "passive"))
      (node (ref "C18") (pin "2") (pinfunction "2_2") (pintype "passive"))
      (node (ref "C19") (pin "1") (pinfunction "1_1") (pintype "passive"))
      (node (ref "C2") (pin "2") (pinfunction "2_2") (pintype "passive"))
      (node (ref "C20") (pin "1") (pinfunction "1_1") (pintype "passive"))
      (node (ref "C21") (pin "2") (pinfunction "2_2") (pintype "passive"))
      (node (ref "C22") (pin "1") (pinfunction "1_1") (pintype "passive"))
      (node (ref "C23") (pin "2") (pinfunction "2_2") (pintype "passive"))
      (node (ref "C24") (pin "2") (pinfunction "2_2") (pintype "passive"))
      (node (ref "C25") (pin "2") (pinfunction "2_2") (pintype "passive"))
      (node (ref "C29") (pin "2") (pinfunction "2_2") (pintype "passive"))
      (node (ref "C3") (pin "2") (pinfunction "2_2") (pintype "passive"))
      (node (ref "C30") (pin "2") (pinfunction "2_2") (pintype "passive"))
      (node (ref "C32") (pin "2") (pinfunction "2_2") (pintype "passive"))
      (node (ref "C33") (pin "2") (pinfunction "2_2") (pintype "passive"))
      (node (ref "C4") (pin "1") (pinfunction "1_1") (pintype "passive"))
      (node (ref "C5") (pin "2") (pinfunction "2_2") (pintype "passive"))
      (node (ref "C6") (pin "2") (pinfunction "2_2") (pintype "passive"))
      (node (ref "C7") (pin "1") (pinfunction "1_1") (pintype "passive"))
      (node (ref "C8") (pin "1") (pinfunction "1_1") (pintype "passive"))
      (node (ref "C9") (pin "1") (pinfunction "1_1") (pintype "passive"))
      (node (ref "D3") (pin "A") (pinfunction "A_A") (pintype "passive"))
      (node (ref "IC1") (pin "10") (pinfunction "VSSB_10") (pintype "passive"))
      (node (ref "IC1") (pin "12") (pinfunction "VBOOST_12") (pintype "passive"))
      (node (ref "IC1") (pin "13") (pinfunction "VBAT_13") (pintype "passive"))
      (node (ref "IC1") (pin "14") (pinfunction "VSSD_1_14") (pintype "passive"))
      (node (ref "IC1") (pin "38") (pinfunction "VSSD_2_38") (pintype "passive"))
      (node (ref "IC1") (pin "64") (pinfunction "VSSA_1_64") (pintype "passive"))
      (node (ref "IC1") (pin "66") (pinfunction "VSSD_3_66") (pintype "passive"))
      (node (ref "IC1") (pin "87") (pinfunction "VSSD_4_87") (pintype "passive"))
      (node (ref "IC2") (pin "10") (pinfunction "AGND_10") (pintype "input"))
      (node (ref "IC2") (pin "12") (pinfunction "GND_12") (pintype "input"))
      (node (ref "IC2") (pin "14") (pinfunction "RESEVED_14") (pintype "input"))
      (node (ref "IC2") (pin "26") (pinfunction "GND_26") (pintype "input"))
      (node (ref "IC2") (pin "28") (pinfunction "GND_28") (pintype "input"))
      (node (ref "IC2") (pin "41") (pinfunction "GND_41") (pintype "input"))
      (node (ref "IC2") (pin "53") (pinfunction "GND_53") (pintype "input"))
      (node (ref "IC2") (pin "56") (pinfunction "GND_56") (pintype "input"))
      (node (ref "IC2") (pin "6") (pinfunction "AGND_6") (pintype "input"))
      (node (ref "IC2") (pin "EPAD") (pinfunction "EPAD_EPAD") (pintype "passive"))
      (node (ref "IC2") (pin "P$1") (pinfunction "EPAD_P$1") (pintype "passive"))
      (node (ref "IC2") (pin "P$10") (pinfunction "EPAD_P$10") (pintype "passive"))
      (node (ref "IC2") (pin "P$11") (pinfunction "EPAD_P$11") (pintype "passive"))
      (node (ref "IC2") (pin "P$12") (pinfunction "EPAD_P$12") (pintype "passive"))
      (node (ref "IC2") (pin "P$13") (pinfunction "EPAD_P$13") (pintype "passive"))
      (node (ref "IC2") (pin "P$14") (pinfunction "EPAD_P$14") (pintype "passive"))
      (node (ref "IC2") (pin "P$15") (pinfunction "EPAD_P$15") (pintype "passive"))
      (node (ref "IC2") (pin "P$16") (pinfunction "EPAD_P$16") (pintype "passive"))
      (node (ref "IC2") (pin "P$2") (pinfunction "EPAD_P$2") (pintype "passive"))
      (node (ref "IC2") (pin "P$3") (pinfunction "EPAD_P$3") (pintype "passive"))
      (node (ref "IC2") (pin "P$4") (pinfunction "EPAD_P$4") (pintype "passive"))
      (node (ref "IC2") (pin "P$5") (pinfunction "EPAD_P$5") (pintype "passive"))
      (node (ref "IC2") (pin "P$6") (pinfunction "EPAD_P$6") (pintype "passive"))
      (node (ref "IC2") (pin "P$7") (pinfunction "EPAD_P$7") (pintype "passive"))
      (node (ref "IC2") (pin "P$8") (pinfunction "EPAD_P$8") (pintype "passive"))
      (node (ref "IC2") (pin "P$9") (pinfunction "EPAD_P$9") (pintype "passive"))
      (node (ref "IC4") (pin "2") (pinfunction "GND_2") (pintype "power_in"))
      (node (ref "JP1") (pin "2") (pinfunction "2_2") (pintype "passive"))
      (node (ref "JP11") (pin "2") (pinfunction "2_2") (pintype "passive"))
      (node (ref "JP11") (pin "3") (pinfunction "3_3") (pintype "passive"))
      (node (ref "JP2") (pin "2") (pinfunction "2_2") (pintype "passive"))
      (node (ref "JP3") (pin "2") (pinfunction "2_2") (pintype "passive"))
      (node (ref "JP4") (pin "2") (pinfunction "2_2") (pintype "passive"))
      (node (ref "JP5") (pin "2") (pinfunction "2_2") (pintype "passive"))
      (node (ref "JP6") (pin "1") (pinfunction "1_1") (pintype "passive"))
      (node (ref "JP7") (pin "2") (pinfunction "2_2") (pintype "passive"))
      (node (ref "JP9") (pin "2") (pinfunction "2_2") (pintype "passive"))
      (node (ref "LED1") (pin "C") (pinfunction "C_C") (pintype "passive"))
      (node (ref "LED2") (pin "C") (pinfunction "C_C") (pintype "passive"))
      (node (ref "LED5") (pin "C") (pinfunction "C_C") (pintype "passive"))
      (node (ref "R14") (pin "1") (pinfunction "1_1") (pintype "passive"))
      (node (ref "R15") (pin "1") (pinfunction "1_1") (pintype "passive"))
      (node (ref "R3") (pin "1") (pinfunction "1_1") (pintype "passive"))
      (node (ref "R9") (pin "1") (pinfunction "1_1") (pintype "passive"))
      (node (ref "REG3V3") (pin "2") (pinfunction "GND_2") (pintype "bidirectional"))
      (node (ref "REG3V3") (pin "3") (pinfunction "GND_3") (pintype "bidirectional"))
      (node (ref "REG3V3") (pin "6") (pinfunction "GND_6") (pintype "bidirectional"))
      (node (ref "REG3V3") (pin "7") (pinfunction "GND_7") (pintype "bidirectional"))
      (node (ref "REG5V0") (pin "2") (pinfunction "GND_2") (pintype "bidirectional"))
      (node (ref "REG5V0") (pin "3") (pinfunction "GND_3") (pintype "bidirectional"))
      (node (ref "REG5V0") (pin "6") (pinfunction "GND_6") (pintype "bidirectional"))
      (node (ref "REG5V0") (pin "7") (pinfunction "GND_7") (pintype "bidirectional"))
      (node (ref "S2") (pin "3") (pinfunction "2_3") (pintype "passive"))
      (node (ref "U$5") (pin "GND") (pinfunction "GND_GND") (pintype "bidirectional"))
      (node (ref "U$6") (pin "GND") (pinfunction "GND_GND") (pintype "bidirectional"))
      (node (ref "Z1") (pin "A") (pinfunction "A_A") (pintype "passive"))
      (node (ref "Z2") (pin "A") (pinfunction "A_A") (pintype "passive"))
      (node (ref "Z3") (pin "A") (pinfunction "A_A") (pintype "passive"))
      (node (ref "Z4") (pin "A") (pinfunction "A_A") (pintype "passive"))
      (node (ref "Z5") (pin "A") (pinfunction "A_A") (pintype "passive"))
      (node (ref "Z6") (pin "A") (pinfunction "A_A") (pintype "passive"))
    )
    (net (code "86") (name "Net-(D1-PadA)") (class "Default")
      (node (ref "D1") (pin "A") (pinfunction "A_A") (pintype "passive"))
      (node (ref "JP6") (pin "2") (pinfunction "2_2") (pintype "passive"))
    )
    (net (code "87") (name "Net-(IC1-P15_6_DP)") (class "Default")
      (node (ref "IC1") (pin "35") (pinfunction "P15_6_DP_35") (pintype "passive"))
      (node (ref "R6") (pin "2") (pinfunction "2_2") (pintype "passive"))
    )
    (net (code "88") (name "Net-(IC1-P15_7_DM)") (class "Default")
      (node (ref "IC1") (pin "36") (pinfunction "P15_7_DM_36") (pintype "passive"))
      (node (ref "R5") (pin "2") (pinfunction "2_2") (pintype "passive"))
    )
    (net (code "89") (name "Net-(IC1-VCCA_1)") (class "Default")
      (node (ref "C20") (pin "2") (pinfunction "2_2") (pintype "passive"))
      (node (ref "IC1") (pin "63") (pinfunction "VCCA_1_63") (pintype "passive"))
    )
    (net (code "90") (name "Net-(IC2-PD7{slash}FD15)") (class "Default")
      (node (ref "IC2") (pin "52") (pinfunction "PD7/FD15_52") (pintype "bidirectional"))
      (node (ref "R13") (pin "1") (pinfunction "1_1") (pintype "passive"))
      (node (ref "R14") (pin "2") (pinfunction "2_2") (pintype "passive"))
    )
    (net (code "91") (name "Net-(IC2-WAKEUP)") (class "Default")
      (node (ref "IC2") (pin "44") (pinfunction "WAKEUP_44") (pintype "input"))
      (node (ref "R2") (pin "1") (pinfunction "1_1") (pintype "passive"))
    )
    (net (code "92") (name "Net-(IC2-XTALIN)") (class "Default")
      (node (ref "C33") (pin "1") (pinfunction "1_1") (pintype "passive"))
      (node (ref "IC2") (pin "5") (pinfunction "XTALIN_5") (pintype "input"))
      (node (ref "Y2") (pin "2") (pinfunction "2_2") (pintype "passive"))
    )
    (net (code "93") (name "Net-(IC2-XTALOUT)") (class "Default")
      (node (ref "C32") (pin "1") (pinfunction "1_1") (pintype "passive"))
      (node (ref "IC2") (pin "4") (pinfunction "XTALOUT_4") (pintype "input"))
      (node (ref "Y2") (pin "1") (pinfunction "1_1") (pintype "passive"))
    )
    (net (code "94") (name "Net-(IC2-~{RESET})") (class "Default")
      (node (ref "C1") (pin "2") (pinfunction "2_2") (pintype "passive"))
      (node (ref "IC2") (pin "42") (pinfunction "~{RESET}_42") (pintype "input"))
      (node (ref "R1") (pin "1") (pinfunction "1_1") (pintype "passive"))
    )
    (net (code "95") (name "Net-(LED1-PadA)") (class "Default")
      (node (ref "LED1") (pin "A") (pinfunction "A_A") (pintype "passive"))
      (node (ref "R7") (pin "1") (pinfunction "1_1") (pintype "passive"))
    )
    (net (code "96") (name "Net-(LED2-PadA)") (class "Default")
      (node (ref "LED2") (pin "A") (pinfunction "A_A") (pintype "passive"))
      (node (ref "R8") (pin "1") (pinfunction "1_1") (pintype "passive"))
    )
    (net (code "97") (name "Net-(LED5-PadA)") (class "Default")
      (node (ref "LED5") (pin "A") (pinfunction "A_A") (pintype "passive"))
      (node (ref "R18") (pin "1") (pinfunction "1_1") (pintype "passive"))
    )
    (net (code "98") (name "Net-(REG3V3-ADJ)") (class "Default")
      (node (ref "R10") (pin "1") (pinfunction "1_1") (pintype "passive"))
      (node (ref "R15") (pin "2") (pinfunction "2_2") (pintype "passive"))
      (node (ref "REG3V3") (pin "5") (pinfunction "ADJ_5") (pintype "bidirectional"))
    )
    (net (code "99") (name "Net-(REG5V0-ADJ)") (class "Default")
      (node (ref "R4") (pin "1") (pinfunction "1_1") (pintype "passive"))
      (node (ref "R9") (pin "2") (pinfunction "2_2") (pintype "passive"))
      (node (ref "REG5V0") (pin "5") (pinfunction "ADJ_5") (pintype "bidirectional"))
    )
    (net (code "100") (name "VDD") (class "Default")
      (node (ref "C10") (pin "2") (pinfunction "2_2") (pintype "passive"))
      (node (ref "C11") (pin "2") (pinfunction "2_2") (pintype "passive"))
      (node (ref "C12") (pin "2") (pinfunction "2_2") (pintype "passive"))
      (node (ref "C23") (pin "1") (pinfunction "1_1") (pintype "passive"))
      (node (ref "C5") (pin "1") (pinfunction "1_1") (pintype "passive"))
      (node (ref "C6") (pin "1") (pinfunction "1_1") (pintype "passive"))
      (node (ref "C7") (pin "2") (pinfunction "2_2") (pintype "passive"))
      (node (ref "C8") (pin "2") (pinfunction "2_2") (pintype "passive"))
      (node (ref "C9") (pin "2") (pinfunction "2_2") (pintype "passive"))
      (node (ref "IC2") (pin "11") (pinfunction "VCC_11") (pintype "input"))
      (node (ref "IC2") (pin "13") (pinfunction "IFCLK/T0OUT_13") (pintype "bidirectional"))
      (node (ref "IC2") (pin "17") (pinfunction "VCC_17") (pintype "input"))
      (node (ref "IC2") (pin "27") (pinfunction "VCC_27") (pintype "input"))
      (node (ref "IC2") (pin "3") (pinfunction "AVCC_3") (pintype "input"))
      (node (ref "IC2") (pin "32") (pinfunction "VCC_32") (pintype "input"))
      (node (ref "IC2") (pin "43") (pinfunction "VCC_43") (pintype "input"))
      (node (ref "IC2") (pin "55") (pinfunction "VCC_55") (pintype "input"))
      (node (ref "IC2") (pin "7") (pinfunction "AVCC_7") (pintype "input"))
      (node (ref "IC4") (pin "5") (pinfunction "VCC_5") (pintype "power_in"))
      (node (ref "JP11") (pin "5") (pinfunction "5_5") (pintype "passive"))
      (node (ref "R1") (pin "2") (pinfunction "2_2") (pintype "passive"))
      (node (ref "R10") (pin "2") (pinfunction "2_2") (pintype "passive"))
      (node (ref "R11") (pin "2") (pinfunction "2_2") (pintype "passive"))
      (node (ref "R12") (pin "2") (pinfunction "2_2") (pintype "passive"))
      (node (ref "R18") (pin "2") (pinfunction "2_2") (pintype "passive"))
      (node (ref "R2") (pin "2") (pinfunction "2_2") (pintype "passive"))
      (node (ref "REG3V3") (pin "4") (pinfunction "VOUT_4") (pintype "bidirectional"))
      (node (ref "SW1") (pin "A1") (pinfunction "A1_A1") (pintype "bidirectional"))
      (node (ref "SW1") (pin "A2") (pinfunction "A2_A2") (pintype "bidirectional"))
    )
    (net (code "101") (name "unconnected-(IC1-IND-Pad11)") (class "Default")
      (node (ref "IC1") (pin "11") (pinfunction "IND_11") (pintype "passive"))
    )
    (net (code "102") (name "unconnected-(IC1-NC1-Pad40)") (class "Default")
      (node (ref "IC1") (pin "40") (pinfunction "NC1_40") (pintype "passive"))
    )
    (net (code "103") (name "unconnected-(IC1-NC2-Pad41)") (class "Default")
      (node (ref "IC1") (pin "41") (pinfunction "NC2_41") (pintype "passive"))
    )
    (net (code "104") (name "unconnected-(IC1-NC3-Pad57)") (class "Default")
      (node (ref "IC1") (pin "57") (pinfunction "NC3_57") (pintype "passive"))
    )
    (net (code "105") (name "unconnected-(IC1-NC4-Pad58)") (class "Default")
      (node (ref "IC1") (pin "58") (pinfunction "NC4_58") (pintype "passive"))
    )
    (net (code "106") (name "unconnected-(IC1-NC5-Pad59)") (class "Default")
      (node (ref "IC1") (pin "59") (pinfunction "NC5_59") (pintype "passive"))
    )
    (net (code "107") (name "unconnected-(IC1-NC6-Pad60)") (class "Default")
      (node (ref "IC1") (pin "60") (pinfunction "NC6_60") (pintype "passive"))
    )
    (net (code "108") (name "unconnected-(IC1-NC7-Pad61)") (class "Default")
      (node (ref "IC1") (pin "61") (pinfunction "NC7_61") (pintype "passive"))
    )
    (net (code "109") (name "unconnected-(IC1-NC8-Pad62)") (class "Default")
      (node (ref "IC1") (pin "62") (pinfunction "NC8_62") (pintype "passive"))
    )
    (net (code "110") (name "unconnected-(IC2-CLKOUT{slash}T1OUT-Pad54)") (class "Default")
      (node (ref "IC2") (pin "54") (pinfunction "CLKOUT/T1OUT_54") (pintype "input"))
    )
    (net (code "111") (name "unconnected-(IC2-CTL0{slash}FLAGA-Pad29)") (class "Default")
      (node (ref "IC2") (pin "29") (pinfunction "CTL0/FLAGA_29") (pintype "output"))
    )
    (net (code "112") (name "unconnected-(IC2-CTL1{slash}FLAGB-Pad30)") (class "Default")
      (node (ref "IC2") (pin "30") (pinfunction "CTL1/FLAGB_30") (pintype "output"))
    )
    (net (code "113") (name "unconnected-(IC2-CTL2{slash}FLAGC-Pad31)") (class "Default")
      (node (ref "IC2") (pin "31") (pinfunction "CTL2/FLAGC_31") (pintype "output"))
    )
    (net (code "114") (name "unconnected-(IC2-PA0{slash}~{INT0}-Pad33)") (class "Default")
      (node (ref "IC2") (pin "33") (pinfunction "PA0/~{INT0}_33") (pintype "bidirectional"))
    )
    (net (code "115") (name "unconnected-(IC2-PA1{slash}~{INT1}-Pad34)") (class "Default")
      (node (ref "IC2") (pin "34") (pinfunction "PA1/~{INT1}_34") (pintype "bidirectional"))
    )
    (net (code "116") (name "unconnected-(IC2-PA2{slash}SLOE-Pad35)") (class "Default")
      (node (ref "IC2") (pin "35") (pinfunction "PA2/SLOE_35") (pintype "bidirectional"))
    )
    (net (code "117") (name "unconnected-(IC2-PA3{slash}WU2-Pad36)") (class "Default")
      (node (ref "IC2") (pin "36") (pinfunction "PA3/WU2_36") (pintype "bidirectional"))
    )
    (net (code "118") (name "unconnected-(IC2-PA4{slash}FIFOADR0-Pad37)") (class "Default")
      (node (ref "IC2") (pin "37") (pinfunction "PA4/FIFOADR0_37") (pintype "bidirectional"))
    )
    (net (code "119") (name "unconnected-(IC2-PA5{slash}FIFOADR1-Pad38)") (class "Default")
      (node (ref "IC2") (pin "38") (pinfunction "PA5/FIFOADR1_38") (pintype "bidirectional"))
    )
    (net (code "120") (name "unconnected-(IC2-PA6{slash}PKTEND-Pad39)") (class "Default")
      (node (ref "IC2") (pin "39") (pinfunction "PA6/PKTEND_39") (pintype "bidirectional"))
    )
    (net (code "121") (name "unconnected-(IC2-PA7{slash}FLAGD{slash}~{SLCS}-Pad40)") (class "Default")
      (node (ref "IC2") (pin "40") (pinfunction "PA7/FLAGD/~{SLCS}_40") (pintype "bidirectional"))
    )
    (net (code "122") (name "unconnected-(IC2-PB0{slash}FD0-Pad18)") (class "Default")
      (node (ref "IC2") (pin "18") (pinfunction "PB0/FD0_18") (pintype "bidirectional"))
    )
    (net (code "123") (name "unconnected-(IC2-PB1{slash}FD1-Pad19)") (class "Default")
      (node (ref "IC2") (pin "19") (pinfunction "PB1/FD1_19") (pintype "bidirectional"))
    )
    (net (code "124") (name "unconnected-(IC2-PB3{slash}FD3-Pad21)") (class "Default")
      (node (ref "IC2") (pin "21") (pinfunction "PB3/FD3_21") (pintype "bidirectional"))
    )
    (net (code "125") (name "unconnected-(IC2-PB4{slash}FD4-Pad22)") (class "Default")
      (node (ref "IC2") (pin "22") (pinfunction "PB4/FD4_22") (pintype "bidirectional"))
    )
    (net (code "126") (name "unconnected-(IC2-PB5{slash}FD5-Pad23)") (class "Default")
      (node (ref "IC2") (pin "23") (pinfunction "PB5/FD5_23") (pintype "bidirectional"))
    )
    (net (code "127") (name "unconnected-(IC2-PB6{slash}FD6-Pad24)") (class "Default")
      (node (ref "IC2") (pin "24") (pinfunction "PB6/FD6_24") (pintype "bidirectional"))
    )
    (net (code "128") (name "unconnected-(IC2-PB7{slash}FD7-Pad25)") (class "Default")
      (node (ref "IC2") (pin "25") (pinfunction "PB7/FD7_25") (pintype "bidirectional"))
    )
    (net (code "129") (name "unconnected-(IC2-PD3{slash}FD11-Pad48)") (class "Default")
      (node (ref "IC2") (pin "48") (pinfunction "PD3/FD11_48") (pintype "bidirectional"))
    )
    (net (code "130") (name "unconnected-(IC2-PD4{slash}FD12-Pad49)") (class "Default")
      (node (ref "IC2") (pin "49") (pinfunction "PD4/FD12_49") (pintype "bidirectional"))
    )
    (net (code "131") (name "unconnected-(IC2-PD5{slash}FD13-Pad50)") (class "Default")
      (node (ref "IC2") (pin "50") (pinfunction "PD5/FD13_50") (pintype "bidirectional"))
    )
    (net (code "132") (name "unconnected-(IC2-PD6{slash}FD14-Pad51)") (class "Default")
      (node (ref "IC2") (pin "51") (pinfunction "PD6/FD14_51") (pintype "bidirectional"))
    )
    (net (code "133") (name "unconnected-(IC2-RDY0{slash}SLRD-Pad1)") (class "Default")
      (node (ref "IC2") (pin "1") (pinfunction "RDY0/SLRD_1") (pintype "input"))
    )
    (net (code "134") (name "unconnected-(IC2-RDY1{slash}SLRW-Pad2)") (class "Default")
      (node (ref "IC2") (pin "2") (pinfunction "RDY1/SLRW_2") (pintype "input"))
    )
    (net (code "135") (name "unconnected-(U$5-PadID)") (class "Default")
      (node (ref "U$5") (pin "ID") (pinfunction "ID_ID") (pintype "bidirectional"))
    )
    (net (code "136") (name "unconnected-(U$5-PadMTN4)") (class "Default")
      (node (ref "U$5") (pin "MTN4") (pinfunction "MTN4_MTN4") (pintype "bidirectional"))
    )
    (net (code "137") (name "unconnected-(U$6-PadID)") (class "Default")
      (node (ref "U$6") (pin "ID") (pinfunction "ID_ID") (pintype "bidirectional"))
    )
  )
)
